# MEGA2560_Rev3e_1.net
KiCad netlist of a schematic drawn in Altium Designer
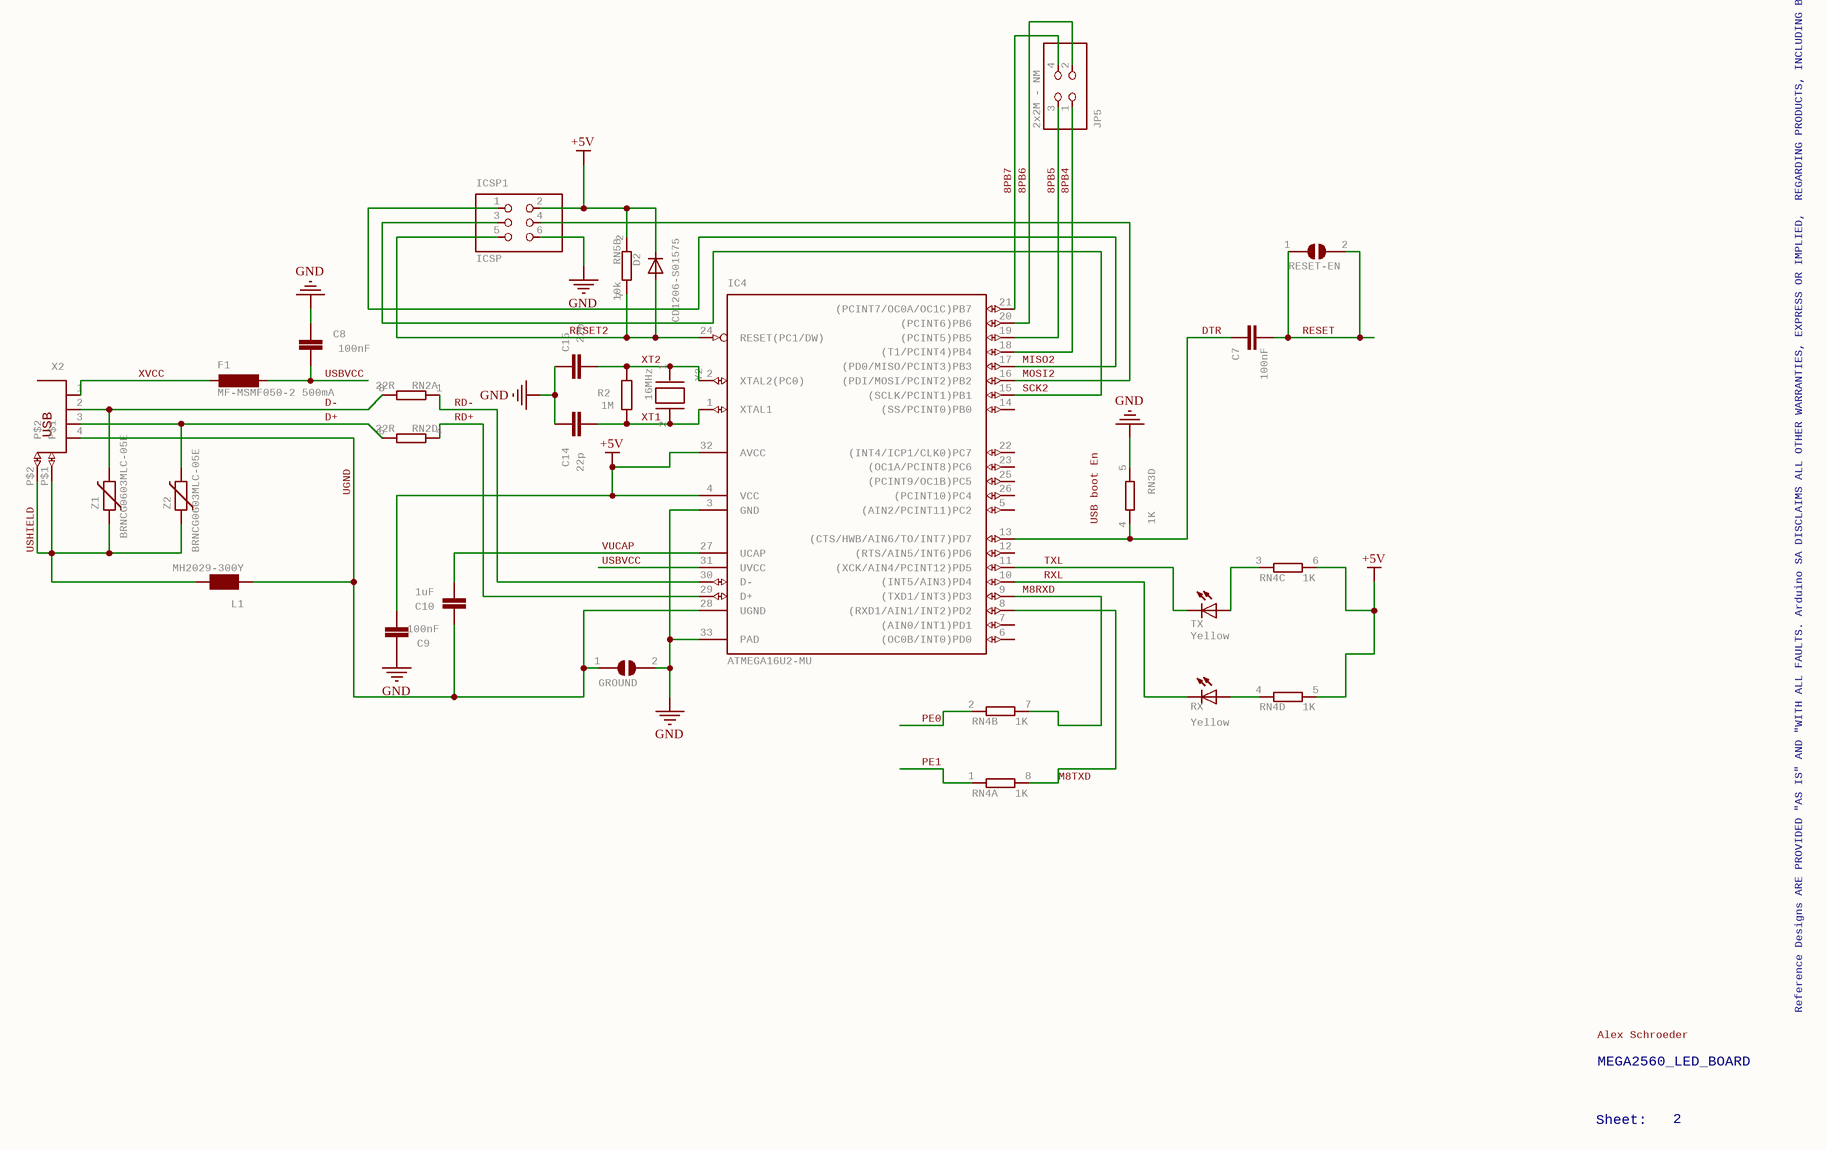
[diagram p0: MEGA2560_Rev3e_1.SchDoc]

(export (version "E")
  (design (tool "Eeschema 10.0.6"))
  (components
    (comp (ref "C7")
      (value "100nF")
      (footprint "C0603-ROUND")
      (description "100nF 0603 50V")
      (fields (field (name "PART_NUMBER") "cl10b104kbnc"))
      (libsource (lib "") (part "0015_100NF_0603_1"))
    )
    (comp (ref "C8")
      (value "100nF")
      (footprint "C0603-ROUND")
      (description "100nF 0603 50V")
      (fields (field (name "PART_NUMBER") "cl10b104kbnc"))
      (libsource (lib "") (part "0015_100NF_0603_1"))
    )
    (comp (ref "C9")
      (value "100nF")
      (footprint "C0603-ROUND")
      (description "100nF 0603 50V")
      (fields (field (name "PART_NUMBER") "cl10b104kbnc"))
      (libsource (lib "Condensatori") (part "0015_100NF_0603"))
    )
    (comp (ref "C10")
      (value "1uF")
      (footprint "C0603-ROUND")
      (description "1uF 0603")
      (fields (field (name "PART_NUMBER") "1uF_0603/GRM188R61E105KA12D"))
      (libsource (lib "Condensatori") (part "0006_1UF_0603/GRM188R61E105KA12D"))
    )
    (comp (ref "C14")
      (value "22p")
      (footprint "C0603-ROUND")
      (description "22pF 0603")
      (fields (field (name "PART_NUMBER") "22pF_0603"))
      (libsource (lib "Condensatori") (part "0014_22PF_0603"))
    )
    (comp (ref "C15")
      (value "22p")
      (footprint "C0603-ROUND")
      (description "22pF 0603")
      (fields (field (name "PART_NUMBER") "22pF_0603"))
      (libsource (lib "Condensatori") (part "0014_22PF_0603"))
    )
    (comp (ref "D2")
      (value "CD1206-S01575")
      (footprint "MINIMELF")
      (description "small-signal high-speed Switching Diodes   CD1206")
      (libsource (lib "Diodi") (part "0012_CD1206-S01575"))
    )
    (comp (ref "F1")
      (value "MF-MSMF050-2 500mA")
      (footprint "L1812")
      (description "500 mA Multifuse ï¿½ Polyfuse")
      (fields (field (name "PART_NUMBER") "MF-MSMF050-2"))
      (libsource (lib "Protezione") (part "0002_MF-MSMF050-2"))
    )
    (comp (ref "GROUND")
      (value "SJ")
      (footprint "SJ")
      (description "SMD solder JUMPER")
      (libsource (lib "jumper") (part "SJ"))
    )
    (comp (ref "IC4")
      (value "ATMEGA16U2-MU")
      (footprint "MLF32")
      (description "8-bit Microcontroller with 16K Bytes of ISP Flash and USB Controller   ATMEGA16U2-MUR")
      (fields (field (name "PART_NUMBER") "ATMEGA16U2-MUR"))
      (libsource (lib "IntegratedCircuits") (part "0007_ATMEGA16U2-MUR"))
    )
    (comp (ref "ICSP1")
      (value "ICSP")
      (footprint "2X03")
      (description "3x2 M V h 8,5 mm p2,54")
      (fields (field (name "PART_NUMBER") "PH254-203DF118A00V") (field (name "LIBRARYNAME") "Connettori"))
      (libsource (lib "Connettori") (part "0114_PH254-203DF118A00V"))
    )
    (comp (ref "JP5")
      (value "2x2M - NM")
      (footprint "2X02")
      (description "PIN HEADER")
      (libsource (lib "SmartPrj") (part "PINHD-2X2"))
    )
    (comp (ref "L1")
      (value "MH2029-300Y")
      (footprint "0805")
      (description "BLM21")
      (fields (field (name "PART_NUMBER") "BLM21PG300SN1D_/_MH2029-300Y"))
      (libsource (lib "Protezione") (part "0001_BLM21PG300SN1D_/_MH2029-300Y"))
    )
    (comp (ref "R2")
      (value "1M")
      (footprint "R0603-ROUND")
      (description "1M 0603")
      (fields (field (name "PART_NUMBER") "0603_1M") (field (name "LIBRARYNAME") "Resistenze"))
      (libsource (lib "Resistenze") (part "0004_0603_1M"))
    )
    (comp (ref "RESET-EN")
      (value "SJ")
      (footprint "SJ")
      (description "SMD solder JUMPER")
      (libsource (lib "jumper") (part "SJ"))
    )
    (comp (ref "RN2")
      (value "22R")
      (footprint "CAY16")
      (description "22R 064R")
      (fields
        (field (name "PART_NUMBER") "064R_22R_/_CAY16-220J4LF")
        (field (name "LIBRARYNAME") "Resistenze")
      )
      (libsource (lib "Resistenze") (part "0003_064R_22R_/_CAY16-220J4LF"))
    )
    (comp (ref "RN3")
      (value "1K")
      (footprint "CAY16")
      (description "1K 064R")
      (fields
        (field (name "PART_NUMBER") "064R_1K_/_CAY16-102J4LF")
        (field (name "LIBRARYNAME") "Resistenze")
      )
      (libsource (lib "Resistenze") (part "0005_064R_1K_/_CAY16-102J4LF"))
    )
    (comp (ref "RN4")
      (value "1K")
      (footprint "CAY16")
      (description "1K 064R")
      (fields
        (field (name "PART_NUMBER") "064R_1K_/_CAY16-102J4LF")
        (field (name "LIBRARYNAME") "Resistenze")
      )
      (libsource (lib "Resistenze") (part "0005_064R_1K_/_CAY16-102J4LF"))
    )
    (comp (ref "RN5")
      (value "10k")
      (footprint "CAY16")
      (description "10K 064 R")
      (fields
        (field (name "PART_NUMBER") "064R_10K_/_CAY16-103J4LF")
        (field (name "LIBRARYNAME") "Resistenze")
      )
      (libsource (lib "Resistenze") (part "0016_064R_10K_/_CAY16-103J4LF"))
    )
    (comp (ref "RX")
      (value "Yellow")
      (footprint "CHIPLED_0805")
      (description "LED YELLOW - SMD - 0805")
      (fields (field (name "PART_NUMBER") "KPT-2012YC"))
      (libsource (lib "Opto") (part "0044_KPT-2012YC"))
    )
    (comp (ref "TX")
      (value "Yellow")
      (footprint "CHIPLED_0805")
      (description "LED YELLOW - SMD - 0805")
      (fields (field (name "PART_NUMBER") "KPT-2012YC"))
      (libsource (lib "Opto") (part "0044_KPT-2012YC"))
    )
    (comp (ref "X2")
      (value "0056_USB-B-S-RA-WT-SPCC")
      (footprint "PN61729")
      (description "USB - B")
      (fields
        (field (name "USB") "USB")
        (field (name "PART_NUMBER") "USB-B-S-RA-WT-SPCC")
        (field (name "LIBRARYNAME") "Connettori")
      )
      (libsource (lib "Connettori") (part "0056_USB-B-S-RA-WT-SPCC"))
    )
    (comp (ref "Y2")
      (value "16MHz")
      (footprint "QS")
      (description "16MHz THT")
      (fields
        (field (name "PART_NUMBER") "P011052006 16M/FTX16M20S")
        (field (name "LIBRARYNAME") "Cristalli")
      )
      (libsource (lib "Cristalli") (part "0019_P011052006_16M"))
    )
    (comp (ref "Z1")
      (value "BRNCG0603MLC-05E")
      (footprint "CT/CN0603")
      (description "CG0603MLC-05E")
      (libsource (lib "Protezione") (part "0010_BRNCG0603MLC-05E"))
    )
    (comp (ref "Z2")
      (value "BRNCG0603MLC-05E")
      (footprint "CT/CN0603")
      (description "CG0603MLC-05E")
      (libsource (lib "Protezione") (part "0010_BRNCG0603MLC-05E"))
    )
  )
  (nets
    (net (code "1") (name "+5V") (class "Default")
      (node (ref "C9") (pin "1") (pinfunction "1_1") (pintype "passive"))
      (node (ref "D2") (pin "C") (pinfunction "C_C") (pintype "passive"))
      (node (ref "IC4") (pin "32") (pinfunction "AVCC_32") (pintype "power_in"))
      (node (ref "IC4") (pin "4") (pinfunction "VCC_4") (pintype "power_in"))
      (node (ref "ICSP1") (pin "2") (pinfunction "2_2") (pintype "passive"))
      (node (ref "RN4") (pin "5") (pinfunction "2_5") (pintype "passive"))
      (node (ref "RN4") (pin "6") (pinfunction "2_6") (pintype "passive"))
      (node (ref "RN5") (pin "2") (pinfunction "1_2") (pintype "passive"))
    )
    (net (code "2") (name "/8PB4") (class "Default")
      (node (ref "IC4") (pin "18") (pinfunction "(T1/PCINT4)PB4_18") (pintype "bidirectional"))
      (node (ref "JP5") (pin "1") (pinfunction "1_1") (pintype "passive"))
    )
    (net (code "3") (name "/8PB5") (class "Default")
      (node (ref "IC4") (pin "19") (pinfunction "(PCINT5)PB5_19") (pintype "bidirectional"))
      (node (ref "JP5") (pin "3") (pinfunction "3_3") (pintype "passive"))
    )
    (net (code "4") (name "/8PB6") (class "Default")
      (node (ref "IC4") (pin "20") (pinfunction "(PCINT6)PB6_20") (pintype "bidirectional"))
      (node (ref "JP5") (pin "2") (pinfunction "2_2") (pintype "passive"))
    )
    (net (code "5") (name "/8PB7") (class "Default")
      (node (ref "IC4") (pin "21") (pinfunction "(PCINT7/OC0A/OC1C)PB7_21") (pintype "bidirectional"))
      (node (ref "JP5") (pin "4") (pinfunction "4_4") (pintype "passive"))
    )
    (net (code "6") (name "/D+") (class "Default")
      (node (ref "RN2") (pin "5") (pinfunction "2_5") (pintype "passive"))
      (node (ref "X2") (pin "3") (pinfunction "3_3") (pintype "bidirectional"))
      (node (ref "Z2") (pin "2") (pinfunction "2_2") (pintype "passive"))
    )
    (net (code "7") (name "/D-") (class "Default")
      (node (ref "RN2") (pin "8") (pinfunction "2_8") (pintype "passive"))
      (node (ref "X2") (pin "2") (pinfunction "2_2") (pintype "bidirectional"))
      (node (ref "Z1") (pin "2") (pinfunction "2_2") (pintype "passive"))
    )
    (net (code "8") (name "/DTR") (class "Default")
      (node (ref "C7") (pin "1") (pinfunction "1_1") (pintype "passive"))
      (node (ref "IC4") (pin "13") (pinfunction "(CTS/HWB/AIN6/TO/INT7)PD7_13") (pintype "bidirectional"))
      (node (ref "RN3") (pin "4") (pinfunction "1_4") (pintype "passive"))
    )
    (net (code "9") (name "/M8RXD") (class "Default")
      (node (ref "IC4") (pin "9") (pinfunction "(TXD1/INT3)PD3_9") (pintype "bidirectional"))
      (node (ref "RN4") (pin "7") (pinfunction "2_7") (pintype "passive"))
    )
    (net (code "10") (name "/M8TXD") (class "Default")
      (node (ref "IC4") (pin "8") (pinfunction "(RXD1/AIN1/INT2)PD2_8") (pintype "bidirectional"))
      (node (ref "RN4") (pin "8") (pinfunction "2_8") (pintype "passive"))
    )
    (net (code "11") (name "/MISO2") (class "Default")
      (node (ref "IC4") (pin "17") (pinfunction "(PD0/MISO/PCINT3)PB3_17") (pintype "bidirectional"))
      (node (ref "ICSP1") (pin "1") (pinfunction "1_1") (pintype "passive"))
    )
    (net (code "12") (name "/MOSI2") (class "Default")
      (node (ref "IC4") (pin "16") (pinfunction "(PDI/MOSI/PCINT2)PB2_16") (pintype "bidirectional"))
      (node (ref "ICSP1") (pin "4") (pinfunction "4_4") (pintype "passive"))
    )
    (net (code "13") (name "/PE0") (class "Default")
      (node (ref "RN4") (pin "2") (pinfunction "1_2") (pintype "passive"))
    )
    (net (code "14") (name "/PE1") (class "Default")
      (node (ref "RN4") (pin "1") (pinfunction "1_1") (pintype "passive"))
    )
    (net (code "15") (name "/RD+") (class "Default")
      (node (ref "IC4") (pin "29") (pinfunction "D+_29") (pintype "bidirectional"))
      (node (ref "RN2") (pin "4") (pinfunction "1_4") (pintype "passive"))
    )
    (net (code "16") (name "/RD-") (class "Default")
      (node (ref "IC4") (pin "30") (pinfunction "D-_30") (pintype "bidirectional"))
      (node (ref "RN2") (pin "1") (pinfunction "1_1") (pintype "passive"))
    )
    (net (code "17") (name "/RESET") (class "Default")
      (node (ref "C7") (pin "2") (pinfunction "2_2") (pintype "passive"))
      (node (ref "RESET-EN") (pin "1") (pinfunction "1_1") (pintype "passive"))
      (node (ref "RESET-EN") (pin "2") (pinfunction "2_2") (pintype "passive"))
    )
    (net (code "18") (name "/RESET2") (class "Default")
      (node (ref "D2") (pin "A") (pinfunction "A_A") (pintype "passive"))
      (node (ref "IC4") (pin "24") (pinfunction "RESET(PC1/DW)_24") (pintype "input"))
      (node (ref "ICSP1") (pin "5") (pinfunction "5_5") (pintype "passive"))
      (node (ref "RN5") (pin "7") (pinfunction "2_7") (pintype "passive"))
    )
    (net (code "19") (name "/RXL") (class "Default")
      (node (ref "IC4") (pin "10") (pinfunction "(INT5/AIN3)PD4_10") (pintype "bidirectional"))
      (node (ref "RX") (pin "C") (pinfunction "C_C") (pintype "passive"))
    )
    (net (code "20") (name "/SCK2") (class "Default")
      (node (ref "IC4") (pin "15") (pinfunction "(SCLK/PCINT1)PB1_15") (pintype "bidirectional"))
      (node (ref "ICSP1") (pin "3") (pinfunction "3_3") (pintype "passive"))
    )
    (net (code "21") (name "/TXL") (class "Default")
      (node (ref "IC4") (pin "11") (pinfunction "(XCK/AIN4/PCINT12)PD5_11") (pintype "bidirectional"))
      (node (ref "TX") (pin "C") (pinfunction "C_C") (pintype "passive"))
    )
    (net (code "22") (name "/UGND") (class "Default")
      (node (ref "C10") (pin "2") (pinfunction "2_2") (pintype "passive"))
      (node (ref "GROUND") (pin "1") (pinfunction "1_1") (pintype "passive"))
      (node (ref "IC4") (pin "28") (pinfunction "UGND_28") (pintype "power_in"))
      (node (ref "L1") (pin "1") (pinfunction "1_1") (pintype "passive"))
      (node (ref "X2") (pin "4") (pinfunction "4_4") (pintype "bidirectional"))
    )
    (net (code "23") (name "/USBVCC") (class "Default")
      (node (ref "C8") (pin "1") (pinfunction "1_1") (pintype "passive"))
      (node (ref "F1") (pin "1") (pinfunction "1_1") (pintype "passive"))
      (node (ref "IC4") (pin "31") (pinfunction "UVCC_31") (pintype "power_in"))
    )
    (net (code "24") (name "/USHIELD") (class "Default")
      (node (ref "L1") (pin "2") (pinfunction "2_2") (pintype "passive"))
      (node (ref "X2") (pin "P$1") (pinfunction "P$1_P$1") (pintype "bidirectional"))
      (node (ref "X2") (pin "P$2") (pinfunction "P$2_P$2") (pintype "bidirectional"))
      (node (ref "Z1") (pin "1") (pinfunction "1_1") (pintype "passive"))
      (node (ref "Z2") (pin "1") (pinfunction "1_1") (pintype "passive"))
    )
    (net (code "25") (name "/VUCAP") (class "Default")
      (node (ref "C10") (pin "1") (pinfunction "1_1") (pintype "passive"))
      (node (ref "IC4") (pin "27") (pinfunction "UCAP_27") (pintype "passive"))
    )
    (net (code "26") (name "/XT1") (class "Default")
      (node (ref "C14") (pin "1") (pinfunction "1_1") (pintype "passive"))
      (node (ref "IC4") (pin "1") (pinfunction "XTAL1_1") (pintype "bidirectional"))
      (node (ref "R2") (pin "1") (pinfunction "1_1") (pintype "passive"))
      (node (ref "Y2") (pin "2") (pinfunction "2_2") (pintype "passive"))
    )
    (net (code "27") (name "/XT2") (class "Default")
      (node (ref "C15") (pin "1") (pinfunction "1_1") (pintype "passive"))
      (node (ref "IC4") (pin "2") (pinfunction "XTAL2(PC0)_2") (pintype "bidirectional"))
      (node (ref "R2") (pin "2") (pinfunction "2_2") (pintype "passive"))
      (node (ref "Y2") (pin "1") (pinfunction "1_1") (pintype "passive"))
    )
    (net (code "28") (name "/XVCC") (class "Default")
      (node (ref "F1") (pin "2") (pinfunction "2_2") (pintype "passive"))
      (node (ref "X2") (pin "1") (pinfunction "1_1") (pintype "bidirectional"))
    )
    (net (code "29") (name "GND") (class "Default")
      (node (ref "C14") (pin "2") (pinfunction "2_2") (pintype "passive"))
      (node (ref "C15") (pin "2") (pinfunction "2_2") (pintype "passive"))
      (node (ref "C8") (pin "2") (pinfunction "2_2") (pintype "passive"))
      (node (ref "C9") (pin "2") (pinfunction "2_2") (pintype "passive"))
      (node (ref "GROUND") (pin "2") (pinfunction "2_2") (pintype "passive"))
      (node (ref "IC4") (pin "3") (pinfunction "GND_3") (pintype "power_in"))
      (node (ref "IC4") (pin "33") (pinfunction "PAD_33") (pintype "power_in"))
      (node (ref "ICSP1") (pin "6") (pinfunction "6_6") (pintype "passive"))
      (node (ref "RN3") (pin "5") (pinfunction "2_5") (pintype "passive"))
    )
    (net (code "30") (name "Net-(RN4C-1)") (class "Default")
      (node (ref "RN4") (pin "3") (pinfunction "1_3") (pintype "passive"))
      (node (ref "TX") (pin "A") (pinfunction "A_A") (pintype "passive"))
    )
    (net (code "31") (name "Net-(RN4D-1)") (class "Default")
      (node (ref "RN4") (pin "4") (pinfunction "1_4") (pintype "passive"))
      (node (ref "RX") (pin "A") (pinfunction "A_A") (pintype "passive"))
    )
    (net (code "32") (name "unconnected-(IC4-(AIN0{slash}INT1)PD1-Pad7)") (class "Default")
      (node (ref "IC4") (pin "7") (pinfunction "(AIN0/INT1)PD1_7") (pintype "bidirectional"))
    )
    (net (code "33") (name "unconnected-(IC4-(AIN2{slash}PCINT11)PC2-Pad5)") (class "Default")
      (node (ref "IC4") (pin "5") (pinfunction "(AIN2/PCINT11)PC2_5") (pintype "bidirectional"))
    )
    (net (code "34") (name "unconnected-(IC4-(INT4{slash}ICP1{slash}CLK0)PC7-Pad22)") (class "Default")
      (node (ref "IC4") (pin "22") (pinfunction "(INT4/ICP1/CLK0)PC7_22") (pintype "bidirectional"))
    )
    (net (code "35") (name "unconnected-(IC4-(OC0B{slash}INT0)PD0-Pad6)") (class "Default")
      (node (ref "IC4") (pin "6") (pinfunction "(OC0B/INT0)PD0_6") (pintype "bidirectional"))
    )
    (net (code "36") (name "unconnected-(IC4-(OC1A{slash}PCINT8)PC6-Pad23)") (class "Default")
      (node (ref "IC4") (pin "23") (pinfunction "(OC1A/PCINT8)PC6_23") (pintype "bidirectional"))
    )
    (net (code "37") (name "unconnected-(IC4-(PCINT9{slash}OC1B)PC5-Pad25)") (class "Default")
      (node (ref "IC4") (pin "25") (pinfunction "(PCINT9/OC1B)PC5_25") (pintype "bidirectional"))
    )
    (net (code "38") (name "unconnected-(IC4-(PCINT10)PC4-Pad26)") (class "Default")
      (node (ref "IC4") (pin "26") (pinfunction "(PCINT10)PC4_26") (pintype "bidirectional"))
    )
    (net (code "39") (name "unconnected-(IC4-(RTS{slash}AIN5{slash}INT6)PD6-Pad12)") (class "Default")
      (node (ref "IC4") (pin "12") (pinfunction "(RTS/AIN5/INT6)PD6_12") (pintype "bidirectional"))
    )
    (net (code "40") (name "unconnected-(IC4-(SS{slash}PCINT0)PB0-Pad14)") (class "Default")
      (node (ref "IC4") (pin "14") (pinfunction "(SS/PCINT0)PB0_14") (pintype "bidirectional"))
    )
  )
)
